# Power-Input.net
KiCad netlist of a schematic drawn in Altium Designer
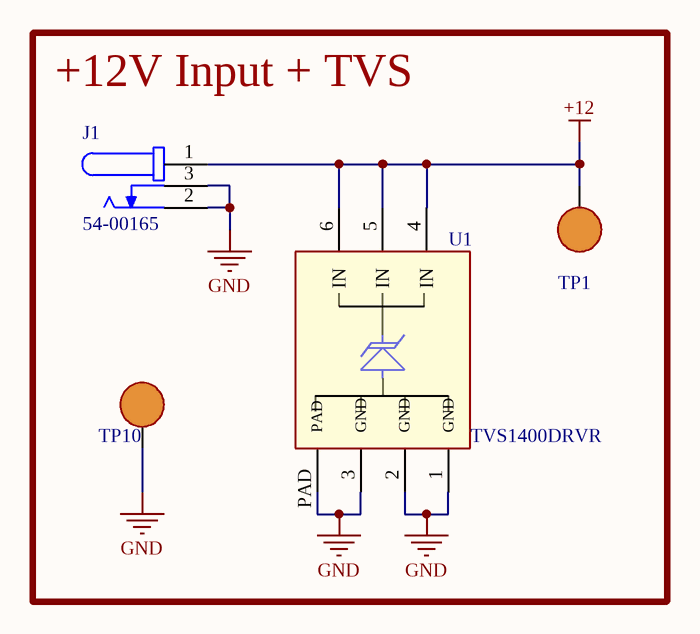
[diagram p0: Power-Input.SchDoc]

(export (version "E")
  (design (tool "Eeschema 10.0.6"))
  (components
    (comp (ref "J1")
      (value "54-00165")
      (footprint "Beethoven-clock:TENSILITY_54-00165")
      (description "Connector, dc jack 5.5x2.5 mm, PCB mount, 90 degrees, silver plated, PA9T, SMT")
      (fields (field (name "MFR") "Same Sky"))
      (libsource (lib "Beethoven-clock") (part "BARREL JACK 2.5MM ID 5.5MM OD"))
    )
    (comp (ref "TP1")
      (value "RCWCTE")
      (footprint "Beethoven-clock:RCWCTE")
      (description "Test Point, Surface Mount")
      (fields (field (name "MFR") "KOA Speer Electronics, Inc."))
      (libsource (lib "Beethoven-clock") (part "TEST POINT"))
    )
    (comp (ref "TP10")
      (value "RCWCTE")
      (footprint "Beethoven-clock:RCWCTE")
      (description "Test Point, Surface Mount")
      (fields (field (name "MFR") "KOA Speer Electronics, Inc."))
      (libsource (lib "Beethoven-clock") (part "TEST POINT"))
    )
    (comp (ref "U1")
      (value "TVS1400DRVR")
      (footprint "Beethoven-clock:6-WDFN-EP")
      (description "UNIDIR  PRECISION SURGE DIODE")
      (fields (field (name "MFR") "Texas Instruments"))
      (libsource (lib "Beethoven-clock") (part "TVS1400DRVR"))
    )
  )
  (nets
    (net (code "1") (name "+12") (class "Default")
      (node (ref "J1") (pin "1") (pinfunction "A_1") (pintype "passive"))
      (node (ref "TP1") (pin "1") (pinfunction "0_1") (pintype "passive"))
      (node (ref "U1") (pin "4") (pinfunction "IN_4") (pintype "passive"))
      (node (ref "U1") (pin "5") (pinfunction "IN_5") (pintype "passive"))
      (node (ref "U1") (pin "6") (pinfunction "IN_6") (pintype "passive"))
    )
    (net (code "2") (name "GND") (class "Default")
      (node (ref "J1") (pin "2") (pinfunction "2_2") (pintype "passive"))
      (node (ref "J1") (pin "3") (pinfunction "3_3") (pintype "passive"))
      (node (ref "TP10") (pin "1") (pinfunction "0_1") (pintype "passive"))
      (node (ref "U1") (pin "1") (pinfunction "GND_1") (pintype "passive"))
      (node (ref "U1") (pin "2") (pinfunction "GND_2") (pintype "passive"))
      (node (ref "U1") (pin "3") (pinfunction "GND_3") (pintype "passive"))
      (node (ref "U1") (pin "PAD") (pinfunction "PAD_PAD") (pintype "passive"))
    )
  )
)
